# DDR3_ZET6_NEW.net
KiCad netlist of a schematic drawn in Altium Designer
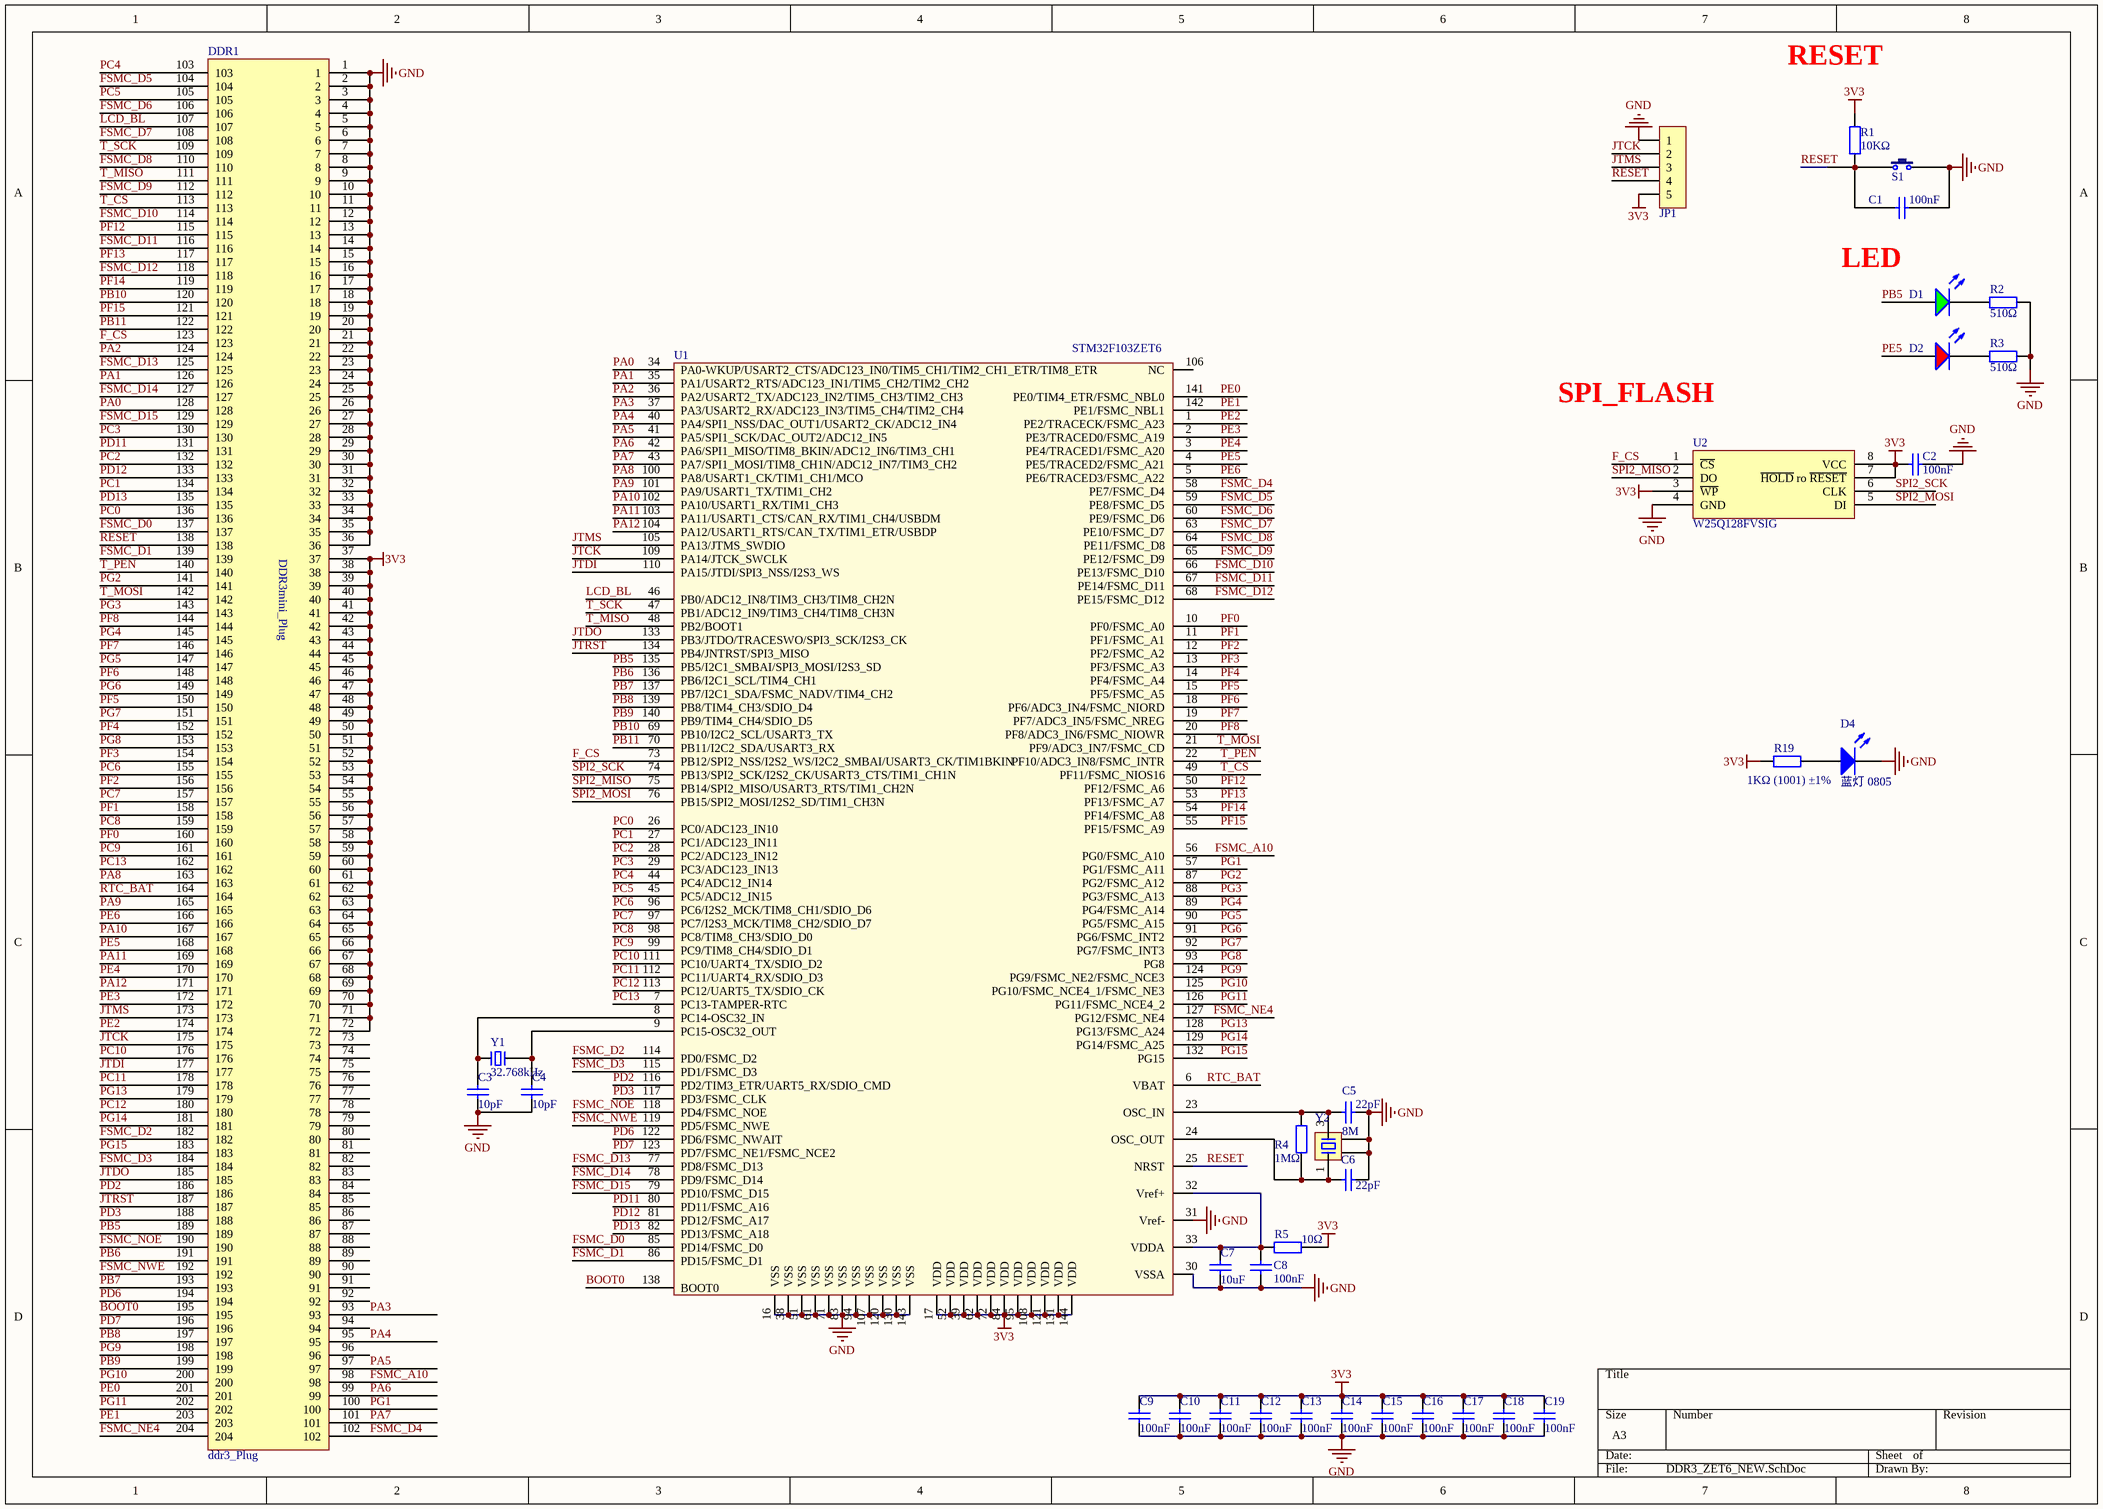
[diagram p0: DDR3_ZET6_NEW.SchDoc]

(export (version "E")
  (design (tool "Eeschema 10.0.6"))
  (components
    (comp (ref "C1")
      (value "100nF")
      (footprint "LC-0805_C")
      (description "贴片电容")
      (libsource (lib "Miscellaneous Devices LC") (part "0805 100nF(104) 10% 50V"))
    )
    (comp (ref "C2")
      (value "100nF")
      (footprint "LC-0805_C")
      (description "贴片电容")
      (libsource (lib "Miscellaneous Devices LC") (part "0805 100nF(104) 10% 50V"))
    )
    (comp (ref "C3")
      (value "10pF")
      (footprint "LC-0805_C")
      (description "贴片电容")
      (libsource (lib "Miscellaneous Devices LC") (part "0805 10pF (100) 5% 50V"))
    )
    (comp (ref "C4")
      (value "10pF")
      (footprint "LC-0805_C")
      (description "贴片电容")
      (libsource (lib "Miscellaneous Devices LC") (part "0805 10pF (100) 5% 50V"))
    )
    (comp (ref "C5")
      (value "22pF")
      (footprint "LC-0805_C")
      (description "贴片电容")
      (libsource (lib "Miscellaneous Devices LC") (part "0805 22pF (220) 5% 50V"))
    )
    (comp (ref "C6")
      (value "22pF")
      (footprint "LC-0805_C")
      (description "贴片电容")
      (libsource (lib "Miscellaneous Devices LC") (part "0805 22pF (220) 5% 50V"))
    )
    (comp (ref "C7")
      (value "10uF")
      (footprint "LC-0805_C")
      (description "贴片电容")
      (libsource (lib "Miscellaneous Devices LC") (part "0805 10uF (106) 10% 25V"))
    )
    (comp (ref "C8")
      (value "100nF")
      (footprint "LC-0805_C")
      (description "贴片电容")
      (libsource (lib "Miscellaneous Devices LC") (part "0805 100nF(104) 10% 50V"))
    )
    (comp (ref "C9")
      (value "100nF")
      (footprint "LC-0805_C")
      (description "贴片电容")
      (libsource (lib "Miscellaneous Devices LC") (part "0805 100nF(104) 10% 50V"))
    )
    (comp (ref "C10")
      (value "100nF")
      (footprint "LC-0805_C")
      (description "贴片电容")
      (libsource (lib "Miscellaneous Devices LC") (part "0805 100nF(104) 10% 50V"))
    )
    (comp (ref "C11")
      (value "100nF")
      (footprint "LC-0805_C")
      (description "贴片电容")
      (libsource (lib "Miscellaneous Devices LC") (part "0805 100nF(104) 10% 50V"))
    )
    (comp (ref "C12")
      (value "100nF")
      (footprint "LC-0805_C")
      (description "贴片电容")
      (libsource (lib "Miscellaneous Devices LC") (part "0805 100nF(104) 10% 50V"))
    )
    (comp (ref "C13")
      (value "100nF")
      (footprint "LC-0805_C")
      (description "贴片电容")
      (libsource (lib "Miscellaneous Devices LC") (part "0805 100nF(104) 10% 50V"))
    )
    (comp (ref "C14")
      (value "100nF")
      (footprint "LC-0805_C")
      (description "贴片电容")
      (libsource (lib "Miscellaneous Devices LC") (part "0805 100nF(104) 10% 50V"))
    )
    (comp (ref "C15")
      (value "100nF")
      (footprint "LC-0805_C")
      (description "贴片电容")
      (libsource (lib "Miscellaneous Devices LC") (part "0805 100nF(104) 10% 50V"))
    )
    (comp (ref "C16")
      (value "100nF")
      (footprint "LC-0805_C")
      (description "贴片电容")
      (libsource (lib "Miscellaneous Devices LC") (part "0805 100nF(104) 10% 50V"))
    )
    (comp (ref "C17")
      (value "100nF")
      (footprint "LC-0805_C")
      (description "贴片电容")
      (libsource (lib "Miscellaneous Devices LC") (part "0805 100nF(104) 10% 50V"))
    )
    (comp (ref "C18")
      (value "100nF")
      (footprint "LC-0805_C")
      (description "贴片电容")
      (libsource (lib "Miscellaneous Devices LC") (part "0805 100nF(104) 10% 50V"))
    )
    (comp (ref "C19")
      (value "100nF")
      (footprint "LC-0805_C")
      (description "贴片电容")
      (libsource (lib "Miscellaneous Devices LC") (part "0805 100nF(104) 10% 50V"))
    )
    (comp (ref "D1")
      (value "翠绿 0805")
      (footprint "LC-0805_LED_S1")
      (description "发光二极管")
      (libsource (lib "Miscellaneous Devices LC") (part "0805 翠绿"))
    )
    (comp (ref "D2")
      (value "红灯 0805")
      (footprint "LC-0805_LED_S1")
      (description "发光二极管")
      (libsource (lib "Miscellaneous Devices LC") (part "0805 红灯"))
    )
    (comp (ref "D4")
      (value "蓝灯 0805")
      (footprint "LC-0805_LED_S1")
      (description "发光二极管")
      (libsource (lib "Miscellaneous Devices LC") (part "0805 蓝灯"))
    )
    (comp (ref "DDR1")
      (value "ddr3_Plug")
      (footprint "DDR3_PLUG_LTE")
      (libsource (lib "my_lib") (part "ddr3_Plug"))
    )
    (comp (ref "JP1")
      (value "HDR-1X5")
      (footprint "HDR-1X5")
      (description "5P接插件")
      (fields (field (name "版权归属") "黎明电子style"))
      (libsource (lib "接插件") (part "Header 5"))
    )
    (comp (ref "R1")
      (value "10KΩ")
      (footprint "LC-0805_R")
      (description "贴片电阻")
      (libsource (lib "Miscellaneous Devices LC") (part "0805 10KΩ (1002) 1%"))
    )
    (comp (ref "R2")
      (value "510Ω")
      (footprint "LC-0805_R")
      (description "贴片电阻")
      (libsource (lib "Miscellaneous Devices LC") (part "0805 510Ω (5100) 1%"))
    )
    (comp (ref "R3")
      (value "510Ω")
      (footprint "LC-0805_R")
      (description "贴片电阻")
      (libsource (lib "Miscellaneous Devices LC") (part "0805 510Ω (5100) 1%"))
    )
    (comp (ref "R4")
      (value "1MΩ")
      (footprint "LC-0805_R")
      (description "贴片电阻")
      (libsource (lib "Miscellaneous Devices LC") (part "0805 1MΩ (1004) 1%"))
    )
    (comp (ref "R5")
      (value "10Ω")
      (footprint "LC-0805_R")
      (description "贴片电阻")
      (libsource (lib "Miscellaneous Devices LC") (part "0805 10Ω (10R0) 1%"))
    )
    (comp (ref "R19")
      (value "1KΩ (1001) ±1%")
      (footprint "LC-0805_R")
      (description "贴片电阻")
      (libsource (lib "Miscellaneous Devices LC") (part "0805 1KΩ (1001) 1%"))
    )
    (comp (ref "S1")
      (value "RESET")
      (footprint "TSW SMD-3*6*2.5")
      (description "3x6轻触开关")
      (fields (field (name "版权归属") "黎明电子style"))
      (libsource (lib "按键-开关") (part "TSW 3x6"))
    )
    (comp (ref "U1")
      (value "STM32F103ZET6")
      (footprint "LC-LQFP-144_20x20x05P")
      (libsource (lib "WarShip V3 STM32103封装库") (part "STM32F103ZET6"))
    )
    (comp (ref "U2")
      (value "W25Q128FVSIG")
      (footprint "LC-SOIC-8_208mil")
      (description "Flash ROM")
      (libsource (lib "Miscellaneous Devices LC") (part "W25Q128FVSIG"))
    )
    (comp (ref "Y1")
      (value "32.768kHz")
      (footprint "XTAL-3215")
      (description "2脚晶振")
      (fields (field (name "版权归属") "黎明电子style"))
      (libsource (lib "保险丝-晶振") (part "XTAL-2"))
    )
    (comp (ref "Y2")
      (value "8M")
      (footprint "XTAL-3225")
      (description "4脚晶振")
      (fields (field (name "版权归属") "黎明电子style"))
      (libsource (lib "保险丝-晶振") (part "XTAL-4"))
    )
  )
  (nets
    (net (code "1") (name "/BOOT0") (class "Default")
      (node (ref "DDR1") (pin "195") (pinfunction "195_195") (pintype "passive"))
      (node (ref "U1") (pin "138") (pinfunction "BOOT0_138") (pintype "passive"))
    )
    (net (code "2") (name "/FSMC_A10") (class "Default")
      (node (ref "DDR1") (pin "98") (pinfunction "98_98") (pintype "passive"))
      (node (ref "U1") (pin "56") (pinfunction "PG0/FSMC_A10_56") (pintype "passive"))
    )
    (net (code "3") (name "/FSMC_D0") (class "Default")
      (node (ref "DDR1") (pin "137") (pinfunction "137_137") (pintype "passive"))
      (node (ref "U1") (pin "85") (pinfunction "PD14/FSMC_D0_85") (pintype "passive"))
    )
    (net (code "4") (name "/FSMC_D1") (class "Default")
      (node (ref "DDR1") (pin "139") (pinfunction "139_139") (pintype "passive"))
      (node (ref "U1") (pin "86") (pinfunction "PD15/FSMC_D1_86") (pintype "passive"))
    )
    (net (code "5") (name "/FSMC_D2") (class "Default")
      (node (ref "DDR1") (pin "182") (pinfunction "182_182") (pintype "passive"))
      (node (ref "U1") (pin "114") (pinfunction "PD0/FSMC_D2_114") (pintype "passive"))
    )
    (net (code "6") (name "/FSMC_D3") (class "Default")
      (node (ref "DDR1") (pin "184") (pinfunction "184_184") (pintype "passive"))
      (node (ref "U1") (pin "115") (pinfunction "PD1/FSMC_D3_115") (pintype "passive"))
    )
    (net (code "7") (name "/FSMC_D4") (class "Default")
      (node (ref "DDR1") (pin "102") (pinfunction "102_102") (pintype "passive"))
      (node (ref "U1") (pin "58") (pinfunction "PE7/FSMC_D4_58") (pintype "passive"))
    )
    (net (code "8") (name "/FSMC_D5") (class "Default")
      (node (ref "DDR1") (pin "104") (pinfunction "104_104") (pintype "passive"))
      (node (ref "U1") (pin "59") (pinfunction "PE8/FSMC_D5_59") (pintype "passive"))
    )
    (net (code "9") (name "/FSMC_D6") (class "Default")
      (node (ref "DDR1") (pin "106") (pinfunction "106_106") (pintype "passive"))
      (node (ref "U1") (pin "60") (pinfunction "PE9/FSMC_D6_60") (pintype "passive"))
    )
    (net (code "10") (name "/FSMC_D7") (class "Default")
      (node (ref "DDR1") (pin "108") (pinfunction "108_108") (pintype "passive"))
      (node (ref "U1") (pin "63") (pinfunction "PE10/FSMC_D7_63") (pintype "passive"))
    )
    (net (code "11") (name "/FSMC_D8") (class "Default")
      (node (ref "DDR1") (pin "110") (pinfunction "110_110") (pintype "passive"))
      (node (ref "U1") (pin "64") (pinfunction "PE11/FSMC_D8_64") (pintype "passive"))
    )
    (net (code "12") (name "/FSMC_D9") (class "Default")
      (node (ref "DDR1") (pin "112") (pinfunction "112_112") (pintype "passive"))
      (node (ref "U1") (pin "65") (pinfunction "PE12/FSMC_D9_65") (pintype "passive"))
    )
    (net (code "13") (name "/FSMC_D10") (class "Default")
      (node (ref "DDR1") (pin "114") (pinfunction "114_114") (pintype "passive"))
      (node (ref "U1") (pin "66") (pinfunction "PE13/FSMC_D10_66") (pintype "passive"))
    )
    (net (code "14") (name "/FSMC_D11") (class "Default")
      (node (ref "DDR1") (pin "116") (pinfunction "116_116") (pintype "passive"))
      (node (ref "U1") (pin "67") (pinfunction "PE14/FSMC_D11_67") (pintype "passive"))
    )
    (net (code "15") (name "/FSMC_D12") (class "Default")
      (node (ref "DDR1") (pin "118") (pinfunction "118_118") (pintype "passive"))
      (node (ref "U1") (pin "68") (pinfunction "PE15/FSMC_D12_68") (pintype "passive"))
    )
    (net (code "16") (name "/FSMC_D13") (class "Default")
      (node (ref "DDR1") (pin "125") (pinfunction "125_125") (pintype "passive"))
      (node (ref "U1") (pin "77") (pinfunction "PD8/FSMC_D13_77") (pintype "passive"))
    )
    (net (code "17") (name "/FSMC_D14") (class "Default")
      (node (ref "DDR1") (pin "127") (pinfunction "127_127") (pintype "passive"))
      (node (ref "U1") (pin "78") (pinfunction "PD9/FSMC_D14_78") (pintype "passive"))
    )
    (net (code "18") (name "/FSMC_D15") (class "Default")
      (node (ref "DDR1") (pin "129") (pinfunction "129_129") (pintype "passive"))
      (node (ref "U1") (pin "79") (pinfunction "PD10/FSMC_D15_79") (pintype "passive"))
    )
    (net (code "19") (name "/FSMC_NE4") (class "Default")
      (node (ref "DDR1") (pin "204") (pinfunction "204_204") (pintype "passive"))
      (node (ref "U1") (pin "127") (pinfunction "PG12/FSMC_NE4_127") (pintype "passive"))
    )
    (net (code "20") (name "/FSMC_NOE") (class "Default")
      (node (ref "DDR1") (pin "190") (pinfunction "190_190") (pintype "passive"))
      (node (ref "U1") (pin "118") (pinfunction "PD4/FSMC_NOE_118") (pintype "passive"))
    )
    (net (code "21") (name "/FSMC_NWE") (class "Default")
      (node (ref "DDR1") (pin "192") (pinfunction "192_192") (pintype "passive"))
      (node (ref "U1") (pin "119") (pinfunction "PD5/FSMC_NWE_119") (pintype "passive"))
    )
    (net (code "22") (name "/F_CS") (class "Default")
      (node (ref "DDR1") (pin "123") (pinfunction "123_123") (pintype "passive"))
      (node (ref "U1") (pin "73") (pinfunction "PB12/SPI2_NSS/I2S2_WS/I2C2_SMBAI/USART3_CK/TIM1BKIN_73") (pintype "passive"))
      (node (ref "U2") (pin "1") (pinfunction "~{CS}_1") (pintype "passive"))
    )
    (net (code "23") (name "/JTCK") (class "Default")
      (node (ref "DDR1") (pin "175") (pinfunction "175_175") (pintype "passive"))
      (node (ref "JP1") (pin "2") (pinfunction "2_2") (pintype "passive"))
      (node (ref "U1") (pin "109") (pinfunction "PA14/JTCK_SWCLK_109") (pintype "passive"))
    )
    (net (code "24") (name "/JTDI") (class "Default")
      (node (ref "DDR1") (pin "177") (pinfunction "177_177") (pintype "passive"))
      (node (ref "U1") (pin "110") (pinfunction "PA15/JTDI/SPI3_NSS/I2S3_WS_110") (pintype "passive"))
    )
    (net (code "25") (name "/JTDO") (class "Default")
      (node (ref "DDR1") (pin "185") (pinfunction "185_185") (pintype "passive"))
      (node (ref "U1") (pin "133") (pinfunction "PB3/JTDO/TRACESWO/SPI3_SCK/I2S3_CK_133") (pintype "passive"))
    )
    (net (code "26") (name "/JTMS") (class "Default")
      (node (ref "DDR1") (pin "173") (pinfunction "173_173") (pintype "passive"))
      (node (ref "JP1") (pin "3") (pinfunction "3_3") (pintype "passive"))
      (node (ref "U1") (pin "105") (pinfunction "PA13/JTMS_SWDIO_105") (pintype "passive"))
    )
    (net (code "27") (name "/JTRST") (class "Default")
      (node (ref "DDR1") (pin "187") (pinfunction "187_187") (pintype "passive"))
      (node (ref "U1") (pin "134") (pinfunction "PB4/JNTRST/SPI3_MISO_134") (pintype "passive"))
    )
    (net (code "28") (name "/LCD_BL") (class "Default")
      (node (ref "DDR1") (pin "107") (pinfunction "107_107") (pintype "passive"))
      (node (ref "U1") (pin "46") (pinfunction "PB0/ADC12_IN8/TIM3_CH3/TIM8_CH2N_46") (pintype "passive"))
    )
    (net (code "29") (name "/PA0") (class "Default")
      (node (ref "DDR1") (pin "128") (pinfunction "128_128") (pintype "passive"))
      (node (ref "U1") (pin "34") (pinfunction "PA0-WKUP/USART2_CTS/ADC123_IN0/TIM5_CH1/TIM2_CH1_ETR/TIM8_ETR_34") (pintype "passive"))
    )
    (net (code "30") (name "/PA1") (class "Default")
      (node (ref "DDR1") (pin "126") (pinfunction "126_126") (pintype "passive"))
      (node (ref "U1") (pin "35") (pinfunction "PA1/USART2_RTS/ADC123_IN1/TIM5_CH2/TIM2_CH2_35") (pintype "passive"))
    )
    (net (code "31") (name "/PA2") (class "Default")
      (node (ref "DDR1") (pin "124") (pinfunction "124_124") (pintype "passive"))
      (node (ref "U1") (pin "36") (pinfunction "PA2/USART2_TX/ADC123_IN2/TIM5_CH3/TIM2_CH3_36") (pintype "passive"))
    )
    (net (code "32") (name "/PA3") (class "Default")
      (node (ref "DDR1") (pin "93") (pinfunction "93_93") (pintype "passive"))
      (node (ref "U1") (pin "37") (pinfunction "PA3/USART2_RX/ADC123_IN3/TIM5_CH4/TIM2_CH4_37") (pintype "passive"))
    )
    (net (code "33") (name "/PA4") (class "Default")
      (node (ref "DDR1") (pin "95") (pinfunction "95_95") (pintype "passive"))
      (node (ref "U1") (pin "40") (pinfunction "PA4/SPI1_NSS/DAC_OUT1/USART2_CK/ADC12_IN4_40") (pintype "passive"))
    )
    (net (code "34") (name "/PA5") (class "Default")
      (node (ref "DDR1") (pin "97") (pinfunction "97_97") (pintype "passive"))
      (node (ref "U1") (pin "41") (pinfunction "PA5/SPI1_SCK/DAC_OUT2/ADC12_IN5_41") (pintype "passive"))
    )
    (net (code "35") (name "/PA6") (class "Default")
      (node (ref "DDR1") (pin "99") (pinfunction "99_99") (pintype "passive"))
      (node (ref "U1") (pin "42") (pinfunction "PA6/SPI1_MISO/TIM8_BKIN/ADC12_IN6/TIM3_CH1_42") (pintype "passive"))
    )
    (net (code "36") (name "/PA7") (class "Default")
      (node (ref "DDR1") (pin "101") (pinfunction "101_101") (pintype "passive"))
      (node (ref "U1") (pin "43") (pinfunction "PA7/SPI1_MOSI/TIM8_CH1N/ADC12_IN7/TIM3_CH2_43") (pintype "passive"))
    )
    (net (code "37") (name "/PA8") (class "Default")
      (node (ref "DDR1") (pin "163") (pinfunction "163_163") (pintype "passive"))
      (node (ref "U1") (pin "100") (pinfunction "PA8/USART1_CK/TIM1_CH1/MCO_100") (pintype "passive"))
    )
    (net (code "38") (name "/PA9") (class "Default")
      (node (ref "DDR1") (pin "165") (pinfunction "165_165") (pintype "passive"))
      (node (ref "U1") (pin "101") (pinfunction "PA9/USART1_TX/TIM1_CH2_101") (pintype "passive"))
    )
    (net (code "39") (name "/PA10") (class "Default")
      (node (ref "DDR1") (pin "167") (pinfunction "167_167") (pintype "passive"))
      (node (ref "U1") (pin "102") (pinfunction "PA10/USART1_RX/TIM1_CH3_102") (pintype "passive"))
    )
    (net (code "40") (name "/PA11") (class "Default")
      (node (ref "DDR1") (pin "169") (pinfunction "169_169") (pintype "passive"))
      (node (ref "U1") (pin "103") (pinfunction "PA11/USART1_CTS/CAN_RX/TIM1_CH4/USBDM_103") (pintype "passive"))
    )
    (net (code "41") (name "/PA12") (class "Default")
      (node (ref "DDR1") (pin "171") (pinfunction "171_171") (pintype "passive"))
      (node (ref "U1") (pin "104") (pinfunction "PA12/USART1_RTS/CAN_TX/TIM1_ETR/USBDP_104") (pintype "passive"))
    )
    (net (code "42") (name "/PB5") (class "Default")
      (node (ref "D1") (pin "A") (pinfunction "A_A") (pintype "passive"))
      (node (ref "DDR1") (pin "189") (pinfunction "189_189") (pintype "passive"))
      (node (ref "U1") (pin "135") (pinfunction "PB5/I2C1_SMBAI/SPI3_MOSI/I2S3_SD_135") (pintype "passive"))
    )
    (net (code "43") (name "/PB6") (class "Default")
      (node (ref "DDR1") (pin "191") (pinfunction "191_191") (pintype "passive"))
      (node (ref "U1") (pin "136") (pinfunction "PB6/I2C1_SCL/TIM4_CH1_136") (pintype "passive"))
    )
    (net (code "44") (name "/PB7") (class "Default")
      (node (ref "DDR1") (pin "193") (pinfunction "193_193") (pintype "passive"))
      (node (ref "U1") (pin "137") (pinfunction "PB7/I2C1_SDA/FSMC_NADV/TIM4_CH2_137") (pintype "passive"))
    )
    (net (code "45") (name "/PB8") (class "Default")
      (node (ref "DDR1") (pin "197") (pinfunction "197_197") (pintype "passive"))
      (node (ref "U1") (pin "139") (pinfunction "PB8/TIM4_CH3/SDIO_D4_139") (pintype "passive"))
    )
    (net (code "46") (name "/PB9") (class "Default")
      (node (ref "DDR1") (pin "199") (pinfunction "199_199") (pintype "passive"))
      (node (ref "U1") (pin "140") (pinfunction "PB9/TIM4_CH4/SDIO_D5_140") (pintype "passive"))
    )
    (net (code "47") (name "/PB10") (class "Default")
      (node (ref "DDR1") (pin "120") (pinfunction "120_120") (pintype "passive"))
      (node (ref "U1") (pin "69") (pinfunction "PB10/I2C2_SCL/USART3_TX_69") (pintype "passive"))
    )
    (net (code "48") (name "/PB11") (class "Default")
      (node (ref "DDR1") (pin "122") (pinfunction "122_122") (pintype "passive"))
      (node (ref "U1") (pin "70") (pinfunction "PB11/I2C2_SDA/USART3_RX_70") (pintype "passive"))
    )
    (net (code "49") (name "/PC0") (class "Default")
      (node (ref "DDR1") (pin "136") (pinfunction "136_136") (pintype "passive"))
      (node (ref "U1") (pin "26") (pinfunction "PC0/ADC123_IN10_26") (pintype "passive"))
    )
    (net (code "50") (name "/PC1") (class "Default")
      (node (ref "DDR1") (pin "134") (pinfunction "134_134") (pintype "passive"))
      (node (ref "U1") (pin "27") (pinfunction "PC1/ADC123_IN11_27") (pintype "passive"))
    )
    (net (code "51") (name "/PC2") (class "Default")
      (node (ref "DDR1") (pin "132") (pinfunction "132_132") (pintype "passive"))
      (node (ref "U1") (pin "28") (pinfunction "PC2/ADC123_IN12_28") (pintype "passive"))
    )
    (net (code "52") (name "/PC3") (class "Default")
      (node (ref "DDR1") (pin "130") (pinfunction "130_130") (pintype "passive"))
      (node (ref "U1") (pin "29") (pinfunction "PC3/ADC123_IN13_29") (pintype "passive"))
    )
    (net (code "53") (name "/PC4") (class "Default")
      (node (ref "DDR1") (pin "103") (pinfunction "103_103") (pintype "passive"))
      (node (ref "U1") (pin "44") (pinfunction "PC4/ADC12_IN14_44") (pintype "passive"))
    )
    (net (code "54") (name "/PC5") (class "Default")
      (node (ref "DDR1") (pin "105") (pinfunction "105_105") (pintype "passive"))
      (node (ref "U1") (pin "45") (pinfunction "PC5/ADC12_IN15_45") (pintype "passive"))
    )
    (net (code "55") (name "/PC6") (class "Default")
      (node (ref "DDR1") (pin "155") (pinfunction "155_155") (pintype "passive"))
      (node (ref "U1") (pin "96") (pinfunction "PC6/I2S2_MCK/TIM8_CH1/SDIO_D6_96") (pintype "passive"))
    )
    (net (code "56") (name "/PC7") (class "Default")
      (node (ref "DDR1") (pin "157") (pinfunction "157_157") (pintype "passive"))
      (node (ref "U1") (pin "97") (pinfunction "PC7/I2S3_MCK/TIM8_CH2/SDIO_D7_97") (pintype "passive"))
    )
    (net (code "57") (name "/PC8") (class "Default")
      (node (ref "DDR1") (pin "159") (pinfunction "159_159") (pintype "passive"))
      (node (ref "U1") (pin "98") (pinfunction "PC8/TIM8_CH3/SDIO_D0_98") (pintype "passive"))
    )
    (net (code "58") (name "/PC9") (class "Default")
      (node (ref "DDR1") (pin "161") (pinfunction "161_161") (pintype "passive"))
      (node (ref "U1") (pin "99") (pinfunction "PC9/TIM8_CH4/SDIO_D1_99") (pintype "passive"))
    )
    (net (code "59") (name "/PC10") (class "Default")
      (node (ref "DDR1") (pin "176") (pinfunction "176_176") (pintype "passive"))
      (node (ref "U1") (pin "111") (pinfunction "PC10/UART4_TX/SDIO_D2_111") (pintype "passive"))
    )
    (net (code "60") (name "/PC11") (class "Default")
      (node (ref "DDR1") (pin "178") (pinfunction "178_178") (pintype "passive"))
      (node (ref "U1") (pin "112") (pinfunction "PC11/UART4_RX/SDIO_D3_112") (pintype "passive"))
    )
    (net (code "61") (name "/PC12") (class "Default")
      (node (ref "DDR1") (pin "180") (pinfunction "180_180") (pintype "passive"))
      (node (ref "U1") (pin "113") (pinfunction "PC12/UART5_TX/SDIO_CK_113") (pintype "passive"))
    )
    (net (code "62") (name "/PC13") (class "Default")
      (node (ref "DDR1") (pin "162") (pinfunction "162_162") (pintype "passive"))
      (node (ref "U1") (pin "7") (pinfunction "PC13-TAMPER-RTC_7") (pintype "passive"))
    )
    (net (code "63") (name "/PD2") (class "Default")
      (node (ref "DDR1") (pin "186") (pinfunction "186_186") (pintype "passive"))
      (node (ref "U1") (pin "116") (pinfunction "PD2/TIM3_ETR/UART5_RX/SDIO_CMD_116") (pintype "passive"))
    )
    (net (code "64") (name "/PD3") (class "Default")
      (node (ref "DDR1") (pin "188") (pinfunction "188_188") (pintype "passive"))
      (node (ref "U1") (pin "117") (pinfunction "PD3/FSMC_CLK_117") (pintype "passive"))
    )
    (net (code "65") (name "/PD6") (class "Default")
      (node (ref "DDR1") (pin "194") (pinfunction "194_194") (pintype "passive"))
      (node (ref "U1") (pin "122") (pinfunction "PD6/FSMC_NWAIT_122") (pintype "passive"))
    )
    (net (code "66") (name "/PD7") (class "Default")
      (node (ref "DDR1") (pin "196") (pinfunction "196_196") (pintype "passive"))
      (node (ref "U1") (pin "123") (pinfunction "PD7/FSMC_NE1/FSMC_NCE2_123") (pintype "passive"))
    )
    (net (code "67") (name "/PD11") (class "Default")
      (node (ref "DDR1") (pin "131") (pinfunction "131_131") (pintype "passive"))
      (node (ref "U1") (pin "80") (pinfunction "PD11/FSMC_A16_80") (pintype "passive"))
    )
    (net (code "68") (name "/PD12") (class "Default")
      (node (ref "DDR1") (pin "133") (pinfunction "133_133") (pintype "passive"))
      (node (ref "U1") (pin "81") (pinfunction "PD12/FSMC_A17_81") (pintype "passive"))
    )
    (net (code "69") (name "/PD13") (class "Default")
      (node (ref "DDR1") (pin "135") (pinfunction "135_135") (pintype "passive"))
      (node (ref "U1") (pin "82") (pinfunction "PD13/FSMC_A18_82") (pintype "passive"))
    )
    (net (code "70") (name "/PE0") (class "Default")
      (node (ref "DDR1") (pin "201") (pinfunction "201_201") (pintype "passive"))
      (node (ref "U1") (pin "141") (pinfunction "PE0/TIM4_ETR/FSMC_NBL0_141") (pintype "passive"))
    )
    (net (code "71") (name "/PE1") (class "Default")
      (node (ref "DDR1") (pin "203") (pinfunction "203_203") (pintype "passive"))
      (node (ref "U1") (pin "142") (pinfunction "PE1/FSMC_NBL1_142") (pintype "passive"))
    )
    (net (code "72") (name "/PE2") (class "Default")
      (node (ref "DDR1") (pin "174") (pinfunction "174_174") (pintype "passive"))
      (node (ref "U1") (pin "1") (pinfunction "PE2/TRACECK/FSMC_A23_1") (pintype "passive"))
    )
    (net (code "73") (name "/PE3") (class "Default")
      (node (ref "DDR1") (pin "172") (pinfunction "172_172") (pintype "passive"))
      (node (ref "U1") (pin "2") (pinfunction "PE3/TRACED0/FSMC_A19_2") (pintype "passive"))
    )
    (net (code "74") (name "/PE4") (class "Default")
      (node (ref "DDR1") (pin "170") (pinfunction "170_170") (pintype "passive"))
      (node (ref "U1") (pin "3") (pinfunction "PE4/TRACED1/FSMC_A20_3") (pintype "passive"))
    )
    (net (code "75") (name "/PE5") (class "Default")
      (node (ref "D2") (pin "A") (pinfunction "A_A") (pintype "passive"))
      (node (ref "DDR1") (pin "168") (pinfunction "168_168") (pintype "passive"))
      (node (ref "U1") (pin "4") (pinfunction "PE5/TRACED2/FSMC_A21_4") (pintype "passive"))
    )
    (net (code "76") (name "/PE6") (class "Default")
      (node (ref "DDR1") (pin "166") (pinfunction "166_166") (pintype "passive"))
      (node (ref "U1") (pin "5") (pinfunction "PE6/TRACED3/FSMC_A22_5") (pintype "passive"))
    )
    (net (code "77") (name "/PF0") (class "Default")
      (node (ref "DDR1") (pin "160") (pinfunction "160_160") (pintype "passive"))
      (node (ref "U1") (pin "10") (pinfunction "PF0/FSMC_A0_10") (pintype "passive"))
    )
    (net (code "78") (name "/PF1") (class "Default")
      (node (ref "DDR1") (pin "158") (pinfunction "158_158") (pintype "passive"))
      (node (ref "U1") (pin "11") (pinfunction "PF1/FSMC_A1_11") (pintype "passive"))
    )
    (net (code "79") (name "/PF2") (class "Default")
      (node (ref "DDR1") (pin "156") (pinfunction "156_156") (pintype "passive"))
      (node (ref "U1") (pin "12") (pinfunction "PF2/FSMC_A2_12") (pintype "passive"))
    )
    (net (code "80") (name "/PF3") (class "Default")
      (node (ref "DDR1") (pin "154") (pinfunction "154_154") (pintype "passive"))
      (node (ref "U1") (pin "13") (pinfunction "PF3/FSMC_A3_13") (pintype "passive"))
    )
    (net (code "81") (name "/PF4") (class "Default")
      (node (ref "DDR1") (pin "152") (pinfunction "152_152") (pintype "passive"))
      (node (ref "U1") (pin "14") (pinfunction "PF4/FSMC_A4_14") (pintype "passive"))
    )
    (net (code "82") (name "/PF5") (class "Default")
      (node (ref "DDR1") (pin "150") (pinfunction "150_150") (pintype "passive"))
      (node (ref "U1") (pin "15") (pinfunction "PF5/FSMC_A5_15") (pintype "passive"))
    )
    (net (code "83") (name "/PF6") (class "Default")
      (node (ref "DDR1") (pin "148") (pinfunction "148_148") (pintype "passive"))
      (node (ref "U1") (pin "18") (pinfunction "PF6/ADC3_IN4/FSMC_NIORD_18") (pintype "passive"))
    )
    (net (code "84") (name "/PF7") (class "Default")
      (node (ref "DDR1") (pin "146") (pinfunction "146_146") (pintype "passive"))
      (node (ref "U1") (pin "19") (pinfunction "PF7/ADC3_IN5/FSMC_NREG_19") (pintype "passive"))
    )
    (net (code "85") (name "/PF8") (class "Default")
      (node (ref "DDR1") (pin "144") (pinfunction "144_144") (pintype "passive"))
      (node (ref "U1") (pin "20") (pinfunction "PF8/ADC3_IN6/FSMC_NIOWR_20") (pintype "passive"))
    )
    (net (code "86") (name "/PF12") (class "Default")
      (node (ref "DDR1") (pin "115") (pinfunction "115_115") (pintype "passive"))
      (node (ref "U1") (pin "50") (pinfunction "PF12/FSMC_A6_50") (pintype "passive"))
    )
    (net (code "87") (name "/PF13") (class "Default")
      (node (ref "DDR1") (pin "117") (pinfunction "117_117") (pintype "passive"))
      (node (ref "U1") (pin "53") (pinfunction "PF13/FSMC_A7_53") (pintype "passive"))
    )
    (net (code "88") (name "/PF14") (class "Default")
      (node (ref "DDR1") (pin "119") (pinfunction "119_119") (pintype "passive"))
      (node (ref "U1") (pin "54") (pinfunction "PF14/FSMC_A8_54") (pintype "passive"))
    )
    (net (code "89") (name "/PF15") (class "Default")
      (node (ref "DDR1") (pin "121") (pinfunction "121_121") (pintype "passive"))
      (node (ref "U1") (pin "55") (pinfunction "PF15/FSMC_A9_55") (pintype "passive"))
    )
    (net (code "90") (name "/PG1") (class "Default")
      (node (ref "DDR1") (pin "100") (pinfunction "100_100") (pintype "passive"))
      (node (ref "U1") (pin "57") (pinfunction "PG1/FSMC_A11_57") (pintype "passive"))
    )
    (net (code "91") (name "/PG2") (class "Default")
      (node (ref "DDR1") (pin "141") (pinfunction "141_141") (pintype "passive"))
      (node (ref "U1") (pin "87") (pinfunction "PG2/FSMC_A12_87") (pintype "passive"))
    )
    (net (code "92") (name "/PG3") (class "Default")
      (node (ref "DDR1") (pin "143") (pinfunction "143_143") (pintype "passive"))
      (node (ref "U1") (pin "88") (pinfunction "PG3/FSMC_A13_88") (pintype "passive"))
    )
    (net (code "93") (name "/PG4") (class "Default")
      (node (ref "DDR1") (pin "145") (pinfunction "145_145") (pintype "passive"))
      (node (ref "U1") (pin "89") (pinfunction "PG4/FSMC_A14_89") (pintype "passive"))
    )
    (net (code "94") (name "/PG5") (class "Default")
      (node (ref "DDR1") (pin "147") (pinfunction "147_147") (pintype "passive"))
      (node (ref "U1") (pin "90") (pinfunction "PG5/FSMC_A15_90") (pintype "passive"))
    )
    (net (code "95") (name "/PG6") (class "Default")
      (node (ref "DDR1") (pin "149") (pinfunction "149_149") (pintype "passive"))
      (node (ref "U1") (pin "91") (pinfunction "PG6/FSMC_INT2_91") (pintype "passive"))
    )
    (net (code "96") (name "/PG7") (class "Default")
      (node (ref "DDR1") (pin "151") (pinfunction "151_151") (pintype "passive"))
      (node (ref "U1") (pin "92") (pinfunction "PG7/FSMC_INT3_92") (pintype "passive"))
    )
    (net (code "97") (name "/PG8") (class "Default")
      (node (ref "DDR1") (pin "153") (pinfunction "153_153") (pintype "passive"))
      (node (ref "U1") (pin "93") (pinfunction "PG8_93") (pintype "passive"))
    )
    (net (code "98") (name "/PG9") (class "Default")
      (node (ref "DDR1") (pin "198") (pinfunction "198_198") (pintype "passive"))
      (node (ref "U1") (pin "124") (pinfunction "PG9/FSMC_NE2/FSMC_NCE3_124") (pintype "passive"))
    )
    (net (code "99") (name "/PG10") (class "Default")
      (node (ref "DDR1") (pin "200") (pinfunction "200_200") (pintype "passive"))
      (node (ref "U1") (pin "125") (pinfunction "PG10/FSMC_NCE4_1/FSMC_NE3_125") (pintype "passive"))
    )
    (net (code "100") (name "/PG11") (class "Default")
      (node (ref "DDR1") (pin "202") (pinfunction "202_202") (pintype "passive"))
      (node (ref "U1") (pin "126") (pinfunction "PG11/FSMC_NCE4_2_126") (pintype "passive"))
    )
    (net (code "101") (name "/PG13") (class "Default")
      (node (ref "DDR1") (pin "179") (pinfunction "179_179") (pintype "passive"))
      (node (ref "U1") (pin "128") (pinfunction "PG13/FSMC_A24_128") (pintype "passive"))
    )
    (net (code "102") (name "/PG14") (class "Default")
      (node (ref "DDR1") (pin "181") (pinfunction "181_181") (pintype "passive"))
      (node (ref "U1") (pin "129") (pinfunction "PG14/FSMC_A25_129") (pintype "passive"))
    )
    (net (code "103") (name "/PG15") (class "Default")
      (node (ref "DDR1") (pin "183") (pinfunction "183_183") (pintype "passive"))
      (node (ref "U1") (pin "132") (pinfunction "PG15_132") (pintype "passive"))
    )
    (net (code "104") (name "/RESET") (class "Default")
      (node (ref "C1") (pin "1") (pinfunction "1_1") (pintype "passive"))
      (node (ref "DDR1") (pin "138") (pinfunction "138_138") (pintype "passive"))
      (node (ref "JP1") (pin "4") (pinfunction "4_4") (pintype "passive"))
      (node (ref "R1") (pin "1") (pinfunction "1_1") (pintype "passive"))
      (node (ref "S1") (pin "1") (pinfunction "1_1") (pintype "passive"))
      (node (ref "U1") (pin "25") (pinfunction "NRST_25") (pintype "passive"))
    )
    (net (code "105") (name "/RTC_BAT") (class "Default")
      (node (ref "DDR1") (pin "164") (pinfunction "164_164") (pintype "passive"))
      (node (ref "U1") (pin "6") (pinfunction "VBAT_6") (pintype "passive"))
    )
    (net (code "106") (name "/SPI2_MISO") (class "Default")
      (node (ref "U1") (pin "75") (pinfunction "PB14/SPI2_MISO/USART3_RTS/TIM1_CH2N_75") (pintype "passive"))
      (node (ref "U2") (pin "2") (pinfunction "DO_2") (pintype "passive"))
    )
    (net (code "107") (name "/SPI2_MOSI") (class "Default")
      (node (ref "U1") (pin "76") (pinfunction "PB15/SPI2_MOSI/I2S2_SD/TIM1_CH3N_76") (pintype "passive"))
      (node (ref "U2") (pin "5") (pinfunction "DI_5") (pintype "passive"))
    )
    (net (code "108") (name "/SPI2_SCK") (class "Default")
      (node (ref "U1") (pin "74") (pinfunction "PB13/SPI2_SCK/I2S2_CK/USART3_CTS/TIM1_CH1N_74") (pintype "passive"))
      (node (ref "U2") (pin "6") (pinfunction "CLK_6") (pintype "passive"))
    )
    (net (code "109") (name "/T_CS") (class "Default")
      (node (ref "DDR1") (pin "113") (pinfunction "113_113") (pintype "passive"))
      (node (ref "U1") (pin "49") (pinfunction "PF11/FSMC_NIOS16_49") (pintype "passive"))
    )
    (net (code "110") (name "/T_MISO") (class "Default")
      (node (ref "DDR1") (pin "111") (pinfunction "111_111") (pintype "passive"))
      (node (ref "U1") (pin "48") (pinfunction "PB2/BOOT1_48") (pintype "passive"))
    )
    (net (code "111") (name "/T_MOSI") (class "Default")
      (node (ref "DDR1") (pin "142") (pinfunction "142_142") (pintype "passive"))
      (node (ref "U1") (pin "21") (pinfunction "PF9/ADC3_IN7/FSMC_CD_21") (pintype "passive"))
    )
    (net (code "112") (name "/T_PEN") (class "Default")
      (node (ref "DDR1") (pin "140") (pinfunction "140_140") (pintype "passive"))
      (node (ref "U1") (pin "22") (pinfunction "PF10/ADC3_IN8/FSMC_INTR_22") (pintype "passive"))
    )
    (net (code "113") (name "/T_SCK") (class "Default")
      (node (ref "DDR1") (pin "109") (pinfunction "109_109") (pintype "passive"))
      (node (ref "U1") (pin "47") (pinfunction "PB1/ADC12_IN9/TIM3_CH4/TIM8_CH3N_47") (pintype "passive"))
    )
    (net (code "114") (name "3V3") (class "Default")
      (node (ref "C10") (pin "2") (pinfunction "2_2") (pintype "passive"))
      (node (ref "C11") (pin "2") (pinfunction "2_2") (pintype "passive"))
      (node (ref "C12") (pin "2") (pinfunction "2_2") (pintype "passive"))
      (node (ref "C13") (pin "2") (pinfunction "2_2") (pintype "passive"))
      (node (ref "C14") (pin "2") (pinfunction "2_2") (pintype "passive"))
      (node (ref "C15") (pin "2") (pinfunction "2_2") (pintype "passive"))
      (node (ref "C16") (pin "2") (pinfunction "2_2") (pintype "passive"))
      (node (ref "C17") (pin "2") (pinfunction "2_2") (pintype "passive"))
      (node (ref "C18") (pin "2") (pinfunction "2_2") (pintype "passive"))
      (node (ref "C19") (pin "2") (pinfunction "2_2") (pintype "passive"))
      (node (ref "C2") (pin "1") (pinfunction "1_1") (pintype "passive"))
      (node (ref "C9") (pin "2") (pinfunction "2_2") (pintype "passive"))
      (node (ref "DDR1") (pin "37") (pinfunction "37_37") (pintype "passive"))
      (node (ref "DDR1") (pin "38") (pinfunction "38_38") (pintype "passive"))
      (node (ref "DDR1") (pin "39") (pinfunction "39_39") (pintype "passive"))
      (node (ref "DDR1") (pin "40") (pinfunction "40_40") (pintype "passive"))
      (node (ref "DDR1") (pin "41") (pinfunction "41_41") (pintype "passive"))
      (node (ref "DDR1") (pin "42") (pinfunction "42_42") (pintype "passive"))
      (node (ref "DDR1") (pin "43") (pinfunction "43_43") (pintype "passive"))
      (node (ref "DDR1") (pin "44") (pinfunction "44_44") (pintype "passive"))
      (node (ref "DDR1") (pin "45") (pinfunction "45_45") (pintype "passive"))
      (node (ref "DDR1") (pin "46") (pinfunction "46_46") (pintype "passive"))
      (node (ref "DDR1") (pin "47") (pinfunction "47_47") (pintype "passive"))
      (node (ref "DDR1") (pin "48") (pinfunction "48_48") (pintype "passive"))
      (node (ref "DDR1") (pin "49") (pinfunction "49_49") (pintype "passive"))
      (node (ref "DDR1") (pin "50") (pinfunction "50_50") (pintype "passive"))
      (node (ref "DDR1") (pin "51") (pinfunction "51_51") (pintype "passive"))
      (node (ref "DDR1") (pin "52") (pinfunction "52_52") (pintype "passive"))
      (node (ref "DDR1") (pin "53") (pinfunction "53_53") (pintype "passive"))
      (node (ref "DDR1") (pin "54") (pinfunction "54_54") (pintype "passive"))
      (node (ref "DDR1") (pin "55") (pinfunction "55_55") (pintype "passive"))
      (node (ref "DDR1") (pin "56") (pinfunction "56_56") (pintype "passive"))
      (node (ref "DDR1") (pin "57") (pinfunction "57_57") (pintype "passive"))
      (node (ref "DDR1") (pin "58") (pinfunction "58_58") (pintype "passive"))
      (node (ref "DDR1") (pin "59") (pinfunction "59_59") (pintype "passive"))
      (node (ref "DDR1") (pin "60") (pinfunction "60_60") (pintype "passive"))
      (node (ref "DDR1") (pin "61") (pinfunction "61_61") (pintype "passive"))
      (node (ref "DDR1") (pin "62") (pinfunction "62_62") (pintype "passive"))
      (node (ref "DDR1") (pin "63") (pinfunction "63_63") (pintype "passive"))
      (node (ref "DDR1") (pin "64") (pinfunction "64_64") (pintype "passive"))
      (node (ref "DDR1") (pin "65") (pinfunction "65_65") (pintype "passive"))
      (node (ref "DDR1") (pin "66") (pinfunction "66_66") (pintype "passive"))
      (node (ref "DDR1") (pin "67") (pinfunction "67_67") (pintype "passive"))
      (node (ref "DDR1") (pin "68") (pinfunction "68_68") (pintype "passive"))
      (node (ref "DDR1") (pin "69") (pinfunction "69_69") (pintype "passive"))
      (node (ref "DDR1") (pin "70") (pinfunction "70_70") (pintype "passive"))
      (node (ref "DDR1") (pin "71") (pinfunction "71_71") (pintype "passive"))
      (node (ref "DDR1") (pin "72") (pinfunction "72_72") (pintype "passive"))
      (node (ref "JP1") (pin "5") (pinfunction "5_5") (pintype "passive"))
      (node (ref "R1") (pin "2") (pinfunction "2_2") (pintype "passive"))
      (node (ref "R19") (pin "1") (pinfunction "1_1") (pintype "passive"))
      (node (ref "R5") (pin "2") (pinfunction "2_2") (pintype "passive"))
      (node (ref "U1") (pin "108") (pinfunction "VDD_108") (pintype "passive"))
      (node (ref "U1") (pin "121") (pinfunction "VDD_121") (pintype "passive"))
      (node (ref "U1") (pin "131") (pinfunction "VDD_131") (pintype "passive"))
      (node (ref "U1") (pin "144") (pinfunction "VDD_144") (pintype "passive"))
      (node (ref "U1") (pin "17") (pinfunction "VDD_17") (pintype "passive"))
      (node (ref "U1") (pin "39") (pinfunction "VDD_39") (pintype "passive"))
      (node (ref "U1") (pin "52") (pinfunction "VDD_52") (pintype "passive"))
      (node (ref "U1") (pin "62") (pinfunction "VDD_62") (pintype "passive"))
      (node (ref "U1") (pin "72") (pinfunction "VDD_72") (pintype "passive"))
      (node (ref "U1") (pin "84") (pinfunction "VDD_84") (pintype "passive"))
      (node (ref "U1") (pin "95") (pinfunction "VDD_95") (pintype "passive"))
      (node (ref "U2") (pin "3") (pinfunction "~{WP}_3") (pintype "passive"))
      (node (ref "U2") (pin "7") (pinfunction "~{HOLD}_ro_~{RESET}_7") (pintype "passive"))
      (node (ref "U2") (pin "8") (pinfunction "VCC_8") (pintype "passive"))
    )
    (net (code "115") (name "GND") (class "Default")
      (node (ref "C1") (pin "2") (pinfunction "2_2") (pintype "passive"))
      (node (ref "C10") (pin "1") (pinfunction "1_1") (pintype "passive"))
      (node (ref "C11") (pin "1") (pinfunction "1_1") (pintype "passive"))
      (node (ref "C12") (pin "1") (pinfunction "1_1") (pintype "passive"))
      (node (ref "C13") (pin "1") (pinfunction "1_1") (pintype "passive"))
      (node (ref "C14") (pin "1") (pinfunction "1_1") (pintype "passive"))
      (node (ref "C15") (pin "1") (pinfunction "1_1") (pintype "passive"))
      (node (ref "C16") (pin "1") (pinfunction "1_1") (pintype "passive"))
      (node (ref "C17") (pin "1") (pinfunction "1_1") (pintype "passive"))
      (node (ref "C18") (pin "1") (pinfunction "1_1") (pintype "passive"))
      (node (ref "C19") (pin "1") (pinfunction "1_1") (pintype "passive"))
      (node (ref "C2") (pin "2") (pinfunction "2_2") (pintype "passive"))
      (node (ref "C3") (pin "1") (pinfunction "1_1") (pintype "passive"))
      (node (ref "C4") (pin "1") (pinfunction "1_1") (pintype "passive"))
      (node (ref "C5") (pin "1") (pinfunction "1_1") (pintype "passive"))
      (node (ref "C6") (pin "1") (pinfunction "1_1") (pintype "passive"))
      (node (ref "C7") (pin "1") (pinfunction "1_1") (pintype "passive"))
      (node (ref "C8") (pin "1") (pinfunction "1_1") (pintype "passive"))
      (node (ref "C9") (pin "1") (pinfunction "1_1") (pintype "passive"))
      (node (ref "D4") (pin "K") (pinfunction "K_K") (pintype "passive"))
      (node (ref "DDR1") (pin "1") (pinfunction "1_1") (pintype "passive"))
      (node (ref "DDR1") (pin "10") (pinfunction "10_10") (pintype "passive"))
      (node (ref "DDR1") (pin "11") (pinfunction "11_11") (pintype "passive"))
      (node (ref "DDR1") (pin "12") (pinfunction "12_12") (pintype "passive"))
      (node (ref "DDR1") (pin "13") (pinfunction "13_13") (pintype "passive"))
      (node (ref "DDR1") (pin "14") (pinfunction "14_14") (pintype "passive"))
      (node (ref "DDR1") (pin "15") (pinfunction "15_15") (pintype "passive"))
      (node (ref "DDR1") (pin "16") (pinfunction "16_16") (pintype "passive"))
      (node (ref "DDR1") (pin "17") (pinfunction "17_17") (pintype "passive"))
      (node (ref "DDR1") (pin "18") (pinfunction "18_18") (pintype "passive"))
      (node (ref "DDR1") (pin "19") (pinfunction "19_19") (pintype "passive"))
      (node (ref "DDR1") (pin "2") (pinfunction "2_2") (pintype "passive"))
      (node (ref "DDR1") (pin "20") (pinfunction "20_20") (pintype "passive"))
      (node (ref "DDR1") (pin "21") (pinfunction "21_21") (pintype "passive"))
      (node (ref "DDR1") (pin "22") (pinfunction "22_22") (pintype "passive"))
      (node (ref "DDR1") (pin "23") (pinfunction "23_23") (pintype "passive"))
      (node (ref "DDR1") (pin "24") (pinfunction "24_24") (pintype "passive"))
      (node (ref "DDR1") (pin "25") (pinfunction "25_25") (pintype "passive"))
      (node (ref "DDR1") (pin "26") (pinfunction "26_26") (pintype "passive"))
      (node (ref "DDR1") (pin "27") (pinfunction "27_27") (pintype "passive"))
      (node (ref "DDR1") (pin "28") (pinfunction "28_28") (pintype "passive"))
      (node (ref "DDR1") (pin "29") (pinfunction "29_29") (pintype "passive"))
      (node (ref "DDR1") (pin "3") (pinfunction "3_3") (pintype "passive"))
      (node (ref "DDR1") (pin "30") (pinfunction "30_30") (pintype "passive"))
      (node (ref "DDR1") (pin "31") (pinfunction "31_31") (pintype "passive"))
      (node (ref "DDR1") (pin "32") (pinfunction "32_32") (pintype "passive"))
      (node (ref "DDR1") (pin "33") (pinfunction "33_33") (pintype "passive"))
      (node (ref "DDR1") (pin "34") (pinfunction "34_34") (pintype "passive"))
      (node (ref "DDR1") (pin "35") (pinfunction "35_35") (pintype "passive"))
      (node (ref "DDR1") (pin "36") (pinfunction "36_36") (pintype "passive"))
      (node (ref "DDR1") (pin "4") (pinfunction "4_4") (pintype "passive"))
      (node (ref "DDR1") (pin "5") (pinfunction "5_5") (pintype "passive"))
      (node (ref "DDR1") (pin "6") (pinfunction "6_6") (pintype "passive"))
      (node (ref "DDR1") (pin "7") (pinfunction "7_7") (pintype "passive"))
      (node (ref "DDR1") (pin "8") (pinfunction "8_8") (pintype "passive"))
      (node (ref "DDR1") (pin "9") (pinfunction "9_9") (pintype "passive"))
      (node (ref "JP1") (pin "1") (pinfunction "1_1") (pintype "passive"))
      (node (ref "R2") (pin "2") (pinfunction "2_2") (pintype "passive"))
      (node (ref "R3") (pin "2") (pinfunction "2_2") (pintype "passive"))
      (node (ref "S1") (pin "2") (pinfunction "2_2") (pintype "passive"))
      (node (ref "U1") (pin "107") (pinfunction "VSS_107") (pintype "passive"))
      (node (ref "U1") (pin "120") (pinfunction "VSS_120") (pintype "passive"))
      (node (ref "U1") (pin "130") (pinfunction "VSS_130") (pintype "passive"))
      (node (ref "U1") (pin "143") (pinfunction "VSS_143") (pintype "passive"))
      (node (ref "U1") (pin "16") (pinfunction "VSS_16") (pintype "passive"))
      (node (ref "U1") (pin "30") (pinfunction "VSSA_30") (pintype "passive"))
      (node (ref "U1") (pin "31") (pinfunction "Vref-_31") (pintype "passive"))
      (node (ref "U1") (pin "38") (pinfunction "VSS_38") (pintype "passive"))
      (node (ref "U1") (pin "51") (pinfunction "VSS_51") (pintype "passive"))
      (node (ref "U1") (pin "61") (pinfunction "VSS_61") (pintype "passive"))
      (node (ref "U1") (pin "71") (pinfunction "VSS_71") (pintype "passive"))
      (node (ref "U1") (pin "83") (pinfunction "VSS_83") (pintype "passive"))
      (node (ref "U1") (pin "94") (pinfunction "VSS_94") (pintype "passive"))
      (node (ref "U2") (pin "4") (pinfunction "GND_4") (pintype "passive"))
      (node (ref "Y2") (pin "2") (pinfunction "2_2") (pintype "passive"))
      (node (ref "Y2") (pin "4") (pinfunction "4_4") (pintype "passive"))
    )
    (net (code "116") (name "Net-(D1-PadK)") (class "Default")
      (node (ref "D1") (pin "K") (pinfunction "K_K") (pintype "passive"))
      (node (ref "R2") (pin "1") (pinfunction "1_1") (pintype "passive"))
    )
    (net (code "117") (name "Net-(D2-PadK)") (class "Default")
      (node (ref "D2") (pin "K") (pinfunction "K_K") (pintype "passive"))
      (node (ref "R3") (pin "1") (pinfunction "1_1") (pintype "passive"))
    )
    (net (code "118") (name "Net-(D4-PadA)") (class "Default")
      (node (ref "D4") (pin "A") (pinfunction "A_A") (pintype "passive"))
      (node (ref "R19") (pin "2") (pinfunction "2_2") (pintype "passive"))
    )
    (net (code "119") (name "Net-(U1-OSC_IN)") (class "Default")
      (node (ref "C5") (pin "2") (pinfunction "2_2") (pintype "passive"))
      (node (ref "R4") (pin "1") (pinfunction "1_1") (pintype "passive"))
      (node (ref "U1") (pin "23") (pinfunction "OSC_IN_23") (pintype "passive"))
      (node (ref "Y2") (pin "3") (pinfunction "3_3") (pintype "passive"))
    )
    (net (code "120") (name "Net-(U1-OSC_OUT)") (class "Default")
      (node (ref "C6") (pin "2") (pinfunction "2_2") (pintype "passive"))
      (node (ref "R4") (pin "2") (pinfunction "2_2") (pintype "passive"))
      (node (ref "U1") (pin "24") (pinfunction "OSC_OUT_24") (pintype "passive"))
      (node (ref "Y2") (pin "1") (pinfunction "1_1") (pintype "passive"))
    )
    (net (code "121") (name "Net-(U1-PC14-OSC32_IN)") (class "Default")
      (node (ref "C3") (pin "2") (pinfunction "2_2") (pintype "passive"))
      (node (ref "U1") (pin "8") (pinfunction "PC14-OSC32_IN_8") (pintype "passive"))
      (node (ref "Y1") (pin "1") (pinfunction "1_1") (pintype "passive"))
    )
    (net (code "122") (name "Net-(U1-PC15-OSC32_OUT)") (class "Default")
      (node (ref "C4") (pin "2") (pinfunction "2_2") (pintype "passive"))
      (node (ref "U1") (pin "9") (pinfunction "PC15-OSC32_OUT_9") (pintype "passive"))
      (node (ref "Y1") (pin "2") (pinfunction "2_2") (pintype "passive"))
    )
    (net (code "123") (name "Net-(U1-VDDA)") (class "Default")
      (node (ref "C7") (pin "2") (pinfunction "2_2") (pintype "passive"))
      (node (ref "C8") (pin "2") (pinfunction "2_2") (pintype "passive"))
      (node (ref "R5") (pin "1") (pinfunction "1_1") (pintype "passive"))
      (node (ref "U1") (pin "32") (pinfunction "Vref+_32") (pintype "passive"))
      (node (ref "U1") (pin "33") (pinfunction "VDDA_33") (pintype "passive"))
    )
    (net (code "124") (name "unconnected-(DDR1-Pad73)") (class "Default")
      (node (ref "DDR1") (pin "73") (pinfunction "73_73") (pintype "passive"))
    )
    (net (code "125") (name "unconnected-(DDR1-Pad74)") (class "Default")
      (node (ref "DDR1") (pin "74") (pinfunction "74_74") (pintype "passive"))
    )
    (net (code "126") (name "unconnected-(DDR1-Pad75)") (class "Default")
      (node (ref "DDR1") (pin "75") (pinfunction "75_75") (pintype "passive"))
    )
    (net (code "127") (name "unconnected-(DDR1-Pad76)") (class "Default")
      (node (ref "DDR1") (pin "76") (pinfunction "76_76") (pintype "passive"))
    )
    (net (code "128") (name "unconnected-(DDR1-Pad77)") (class "Default")
      (node (ref "DDR1") (pin "77") (pinfunction "77_77") (pintype "passive"))
    )
    (net (code "129") (name "unconnected-(DDR1-Pad78)") (class "Default")
      (node (ref "DDR1") (pin "78") (pinfunction "78_78") (pintype "passive"))
    )
    (net (code "130") (name "unconnected-(DDR1-Pad79)") (class "Default")
      (node (ref "DDR1") (pin "79") (pinfunction "79_79") (pintype "passive"))
    )
    (net (code "131") (name "unconnected-(DDR1-Pad80)") (class "Default")
      (node (ref "DDR1") (pin "80") (pinfunction "80_80") (pintype "passive"))
    )
    (net (code "132") (name "unconnected-(DDR1-Pad81)") (class "Default")
      (node (ref "DDR1") (pin "81") (pinfunction "81_81") (pintype "passive"))
    )
    (net (code "133") (name "unconnected-(DDR1-Pad82)") (class "Default")
      (node (ref "DDR1") (pin "82") (pinfunction "82_82") (pintype "passive"))
    )
    (net (code "134") (name "unconnected-(DDR1-Pad83)") (class "Default")
      (node (ref "DDR1") (pin "83") (pinfunction "83_83") (pintype "passive"))
    )
    (net (code "135") (name "unconnected-(DDR1-Pad84)") (class "Default")
      (node (ref "DDR1") (pin "84") (pinfunction "84_84") (pintype "passive"))
    )
    (net (code "136") (name "unconnected-(DDR1-Pad85)") (class "Default")
      (node (ref "DDR1") (pin "85") (pinfunction "85_85") (pintype "passive"))
    )
    (net (code "137") (name "unconnected-(DDR1-Pad86)") (class "Default")
      (node (ref "DDR1") (pin "86") (pinfunction "86_86") (pintype "passive"))
    )
    (net (code "138") (name "unconnected-(DDR1-Pad87)") (class "Default")
      (node (ref "DDR1") (pin "87") (pinfunction "87_87") (pintype "passive"))
    )
    (net (code "139") (name "unconnected-(DDR1-Pad88)") (class "Default")
      (node (ref "DDR1") (pin "88") (pinfunction "88_88") (pintype "passive"))
    )
    (net (code "140") (name "unconnected-(DDR1-Pad89)") (class "Default")
      (node (ref "DDR1") (pin "89") (pinfunction "89_89") (pintype "passive"))
    )
    (net (code "141") (name "unconnected-(DDR1-Pad90)") (class "Default")
      (node (ref "DDR1") (pin "90") (pinfunction "90_90") (pintype "passive"))
    )
    (net (code "142") (name "unconnected-(DDR1-Pad91)") (class "Default")
      (node (ref "DDR1") (pin "91") (pinfunction "91_91") (pintype "passive"))
    )
    (net (code "143") (name "unconnected-(DDR1-Pad92)") (class "Default")
      (node (ref "DDR1") (pin "92") (pinfunction "92_92") (pintype "passive"))
    )
    (net (code "144") (name "unconnected-(DDR1-Pad94)") (class "Default")
      (node (ref "DDR1") (pin "94") (pinfunction "94_94") (pintype "passive"))
    )
    (net (code "145") (name "unconnected-(DDR1-Pad96)") (class "Default")
      (node (ref "DDR1") (pin "96") (pinfunction "96_96") (pintype "passive"))
    )
    (net (code "146") (name "unconnected-(U1-NC-Pad106)") (class "Default")
      (node (ref "U1") (pin "106") (pinfunction "NC_106") (pintype "passive"))
    )
  )
)
